# amica.net
KiCad netlist of a schematic drawn in EAGLE
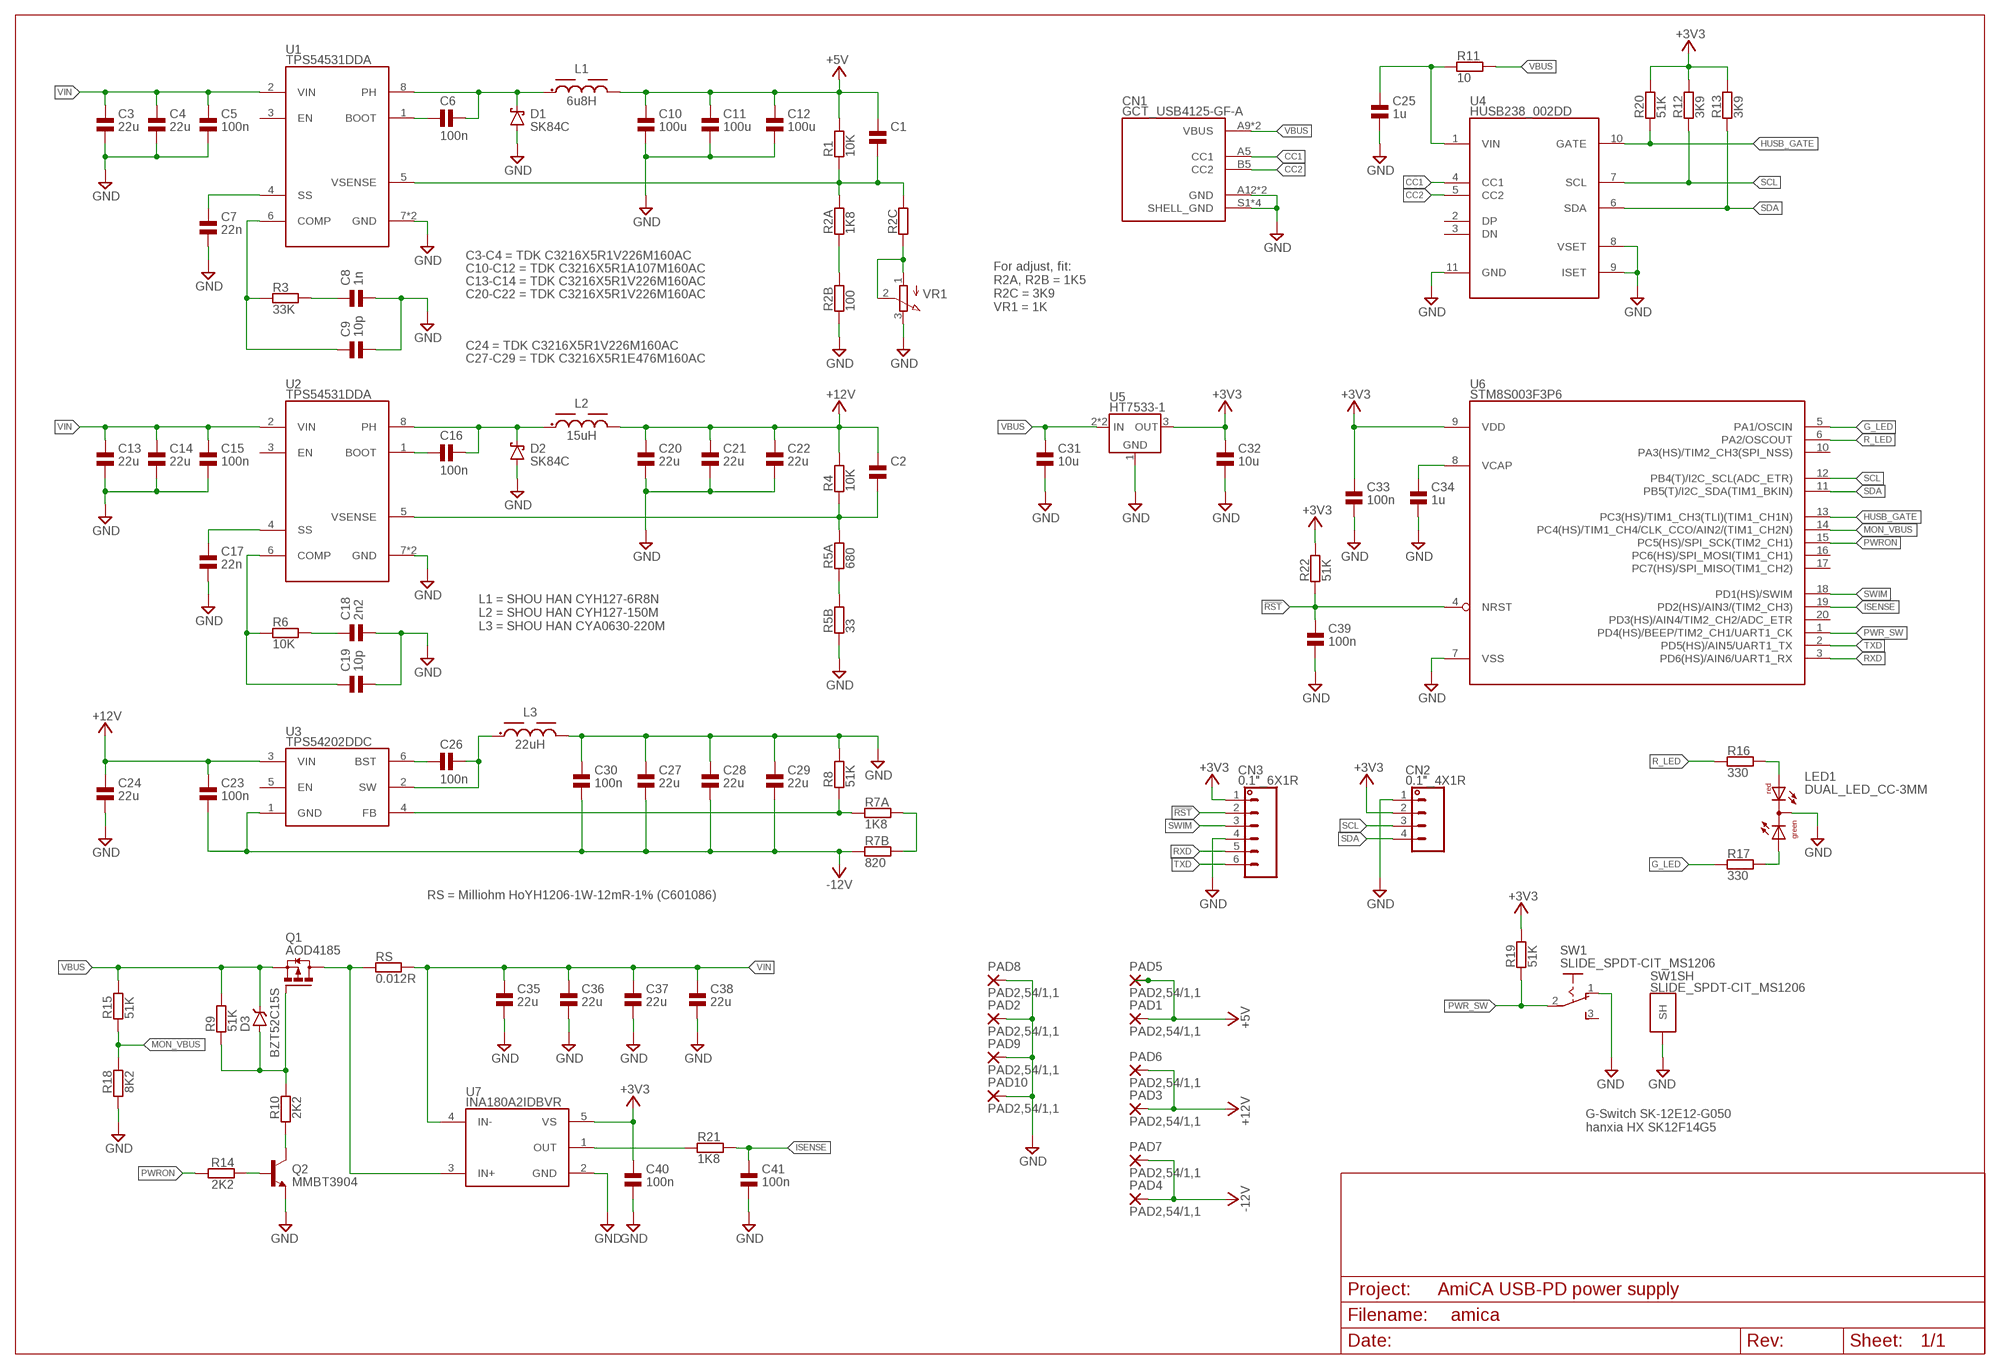
[diagram p0: schematic, sheet 1]

(export (version "E")
  (design (tool "Eeschema 10.0.6"))
  (components
    (comp (ref "C1")
      (value "CAP_NPOL-0603")
      (footprint "eagle-import:0603")
      (libsource (lib "eagle-import") (part "CAP_NPOL0603-"))
    )
    (comp (ref "C2")
      (value "CAP_NPOL-0603")
      (footprint "eagle-import:0603")
      (libsource (lib "eagle-import") (part "CAP_NPOL0603-"))
    )
    (comp (ref "C3")
      (value "22u")
      (footprint "eagle-import:1206")
      (fields (field (name "LCSC_PART") "C12891"))
      (libsource (lib "eagle-import") (part "CAP_NPOL1206-"))
    )
    (comp (ref "C4")
      (value "22u")
      (footprint "eagle-import:1206")
      (fields (field (name "LCSC_PART") "C12891"))
      (libsource (lib "eagle-import") (part "CAP_NPOL1206-"))
    )
    (comp (ref "C5")
      (value "100n")
      (footprint "eagle-import:0603")
      (fields (field (name "LCSC_PART") "C14663"))
      (libsource (lib "eagle-import") (part "CAP_NPOL0603-"))
    )
    (comp (ref "C6")
      (value "100n")
      (footprint "eagle-import:0603")
      (fields (field (name "LCSC_PART") "C14663"))
      (libsource (lib "eagle-import") (part "CAP_NPOL0603-"))
    )
    (comp (ref "C7")
      (value "22n")
      (footprint "eagle-import:0603")
      (fields (field (name "LCSC_PART") "C21122"))
      (libsource (lib "eagle-import") (part "CAP_NPOL0603-"))
    )
    (comp (ref "C8")
      (value "1n")
      (footprint "eagle-import:0603")
      (fields (field (name "LCSC_PART") "C1588"))
      (libsource (lib "eagle-import") (part "CAP_NPOL0603-"))
    )
    (comp (ref "C9")
      (value "10p")
      (footprint "eagle-import:0603")
      (fields (field (name "LCSC_PART") "C1634"))
      (libsource (lib "eagle-import") (part "CAP_NPOL0603-"))
    )
    (comp (ref "C10")
      (value "100u")
      (footprint "eagle-import:1206")
      (fields (field (name "LCSC_PART") "C15008"))
      (libsource (lib "eagle-import") (part "CAP_NPOL1206-"))
    )
    (comp (ref "C11")
      (value "100u")
      (footprint "eagle-import:1206")
      (fields (field (name "LCSC_PART") "C15008"))
      (libsource (lib "eagle-import") (part "CAP_NPOL1206-"))
    )
    (comp (ref "C12")
      (value "100u")
      (footprint "eagle-import:1206")
      (fields (field (name "LCSC_PART") "C15008"))
      (libsource (lib "eagle-import") (part "CAP_NPOL1206-"))
    )
    (comp (ref "C13")
      (value "22u")
      (footprint "eagle-import:1206")
      (fields (field (name "LCSC_PART") "C12891"))
      (libsource (lib "eagle-import") (part "CAP_NPOL1206-"))
    )
    (comp (ref "C14")
      (value "22u")
      (footprint "eagle-import:1206")
      (fields (field (name "LCSC_PART") "C12891"))
      (libsource (lib "eagle-import") (part "CAP_NPOL1206-"))
    )
    (comp (ref "C15")
      (value "100n")
      (footprint "eagle-import:0603")
      (fields (field (name "LCSC_PART") "C14663"))
      (libsource (lib "eagle-import") (part "CAP_NPOL0603-"))
    )
    (comp (ref "C16")
      (value "100n")
      (footprint "eagle-import:0603")
      (fields (field (name "LCSC_PART") "C14663"))
      (libsource (lib "eagle-import") (part "CAP_NPOL0603-"))
    )
    (comp (ref "C17")
      (value "22n")
      (footprint "eagle-import:0603")
      (fields (field (name "LCSC_PART") "C21122"))
      (libsource (lib "eagle-import") (part "CAP_NPOL0603-"))
    )
    (comp (ref "C18")
      (value "2n2")
      (footprint "eagle-import:0603")
      (fields (field (name "LCSC_PART") "C1604"))
      (libsource (lib "eagle-import") (part "CAP_NPOL0603-"))
    )
    (comp (ref "C19")
      (value "10p")
      (footprint "eagle-import:0603")
      (fields (field (name "LCSC_PART") "C1634"))
      (libsource (lib "eagle-import") (part "CAP_NPOL0603-"))
    )
    (comp (ref "C20")
      (value "22u")
      (footprint "eagle-import:1206")
      (fields (field (name "LCSC_PART") "C12891"))
      (libsource (lib "eagle-import") (part "CAP_NPOL1206-"))
    )
    (comp (ref "C21")
      (value "22u")
      (footprint "eagle-import:1206")
      (fields (field (name "LCSC_PART") "C12891"))
      (libsource (lib "eagle-import") (part "CAP_NPOL1206-"))
    )
    (comp (ref "C22")
      (value "22u")
      (footprint "eagle-import:1206")
      (fields (field (name "LCSC_PART") "C12891"))
      (libsource (lib "eagle-import") (part "CAP_NPOL1206-"))
    )
    (comp (ref "C23")
      (value "100n")
      (footprint "eagle-import:0603")
      (fields (field (name "LCSC_PART") "C14663"))
      (libsource (lib "eagle-import") (part "CAP_NPOL0603-"))
    )
    (comp (ref "C24")
      (value "22u")
      (footprint "eagle-import:1206")
      (fields (field (name "LCSC_PART") "C12891"))
      (libsource (lib "eagle-import") (part "CAP_NPOL1206-"))
    )
    (comp (ref "C25")
      (value "1u")
      (footprint "eagle-import:0603")
      (fields (field (name "LCSC_PART") "C15849"))
      (libsource (lib "eagle-import") (part "CAP_NPOL0603-"))
    )
    (comp (ref "C26")
      (value "100n")
      (footprint "eagle-import:0603")
      (fields (field (name "LCSC_PART") "C14663"))
      (libsource (lib "eagle-import") (part "CAP_NPOL0603-"))
    )
    (comp (ref "C27")
      (value "22u")
      (footprint "eagle-import:1206")
      (fields (field (name "LCSC_PART") "C12891"))
      (libsource (lib "eagle-import") (part "CAP_NPOL1206-"))
    )
    (comp (ref "C28")
      (value "22u")
      (footprint "eagle-import:1206")
      (fields (field (name "LCSC_PART") "C12891"))
      (libsource (lib "eagle-import") (part "CAP_NPOL1206-"))
    )
    (comp (ref "C29")
      (value "22u")
      (footprint "eagle-import:1206")
      (fields (field (name "LCSC_PART") "C12891"))
      (libsource (lib "eagle-import") (part "CAP_NPOL1206-"))
    )
    (comp (ref "C30")
      (value "100n")
      (footprint "eagle-import:0603")
      (fields (field (name "LCSC_PART") "C14663"))
      (libsource (lib "eagle-import") (part "CAP_NPOL0603-"))
    )
    (comp (ref "C31")
      (value "10u")
      (footprint "eagle-import:0805")
      (fields (field (name "LCSC_PART") "C15850"))
      (libsource (lib "eagle-import") (part "CAP_NPOL0805-"))
    )
    (comp (ref "C32")
      (value "10u")
      (footprint "eagle-import:0603")
      (fields (field (name "LCSC_PART") "C19702"))
      (libsource (lib "eagle-import") (part "CAP_NPOL0603-"))
    )
    (comp (ref "C33")
      (value "100n")
      (footprint "eagle-import:0603")
      (fields (field (name "LCSC_PART") "C14663"))
      (libsource (lib "eagle-import") (part "CAP_NPOL0603-"))
    )
    (comp (ref "C34")
      (value "1u")
      (footprint "eagle-import:0603")
      (fields (field (name "LCSC_PART") "C15849"))
      (libsource (lib "eagle-import") (part "CAP_NPOL0603-"))
    )
    (comp (ref "C35")
      (value "22u")
      (footprint "eagle-import:1206")
      (fields (field (name "LCSC_PART") "C12891"))
      (libsource (lib "eagle-import") (part "CAP_NPOL1206-"))
    )
    (comp (ref "C36")
      (value "22u")
      (footprint "eagle-import:1206")
      (fields (field (name "LCSC_PART") "C12891"))
      (libsource (lib "eagle-import") (part "CAP_NPOL1206-"))
    )
    (comp (ref "C37")
      (value "22u")
      (footprint "eagle-import:1206")
      (fields (field (name "LCSC_PART") "C12891"))
      (libsource (lib "eagle-import") (part "CAP_NPOL1206-"))
    )
    (comp (ref "C38")
      (value "22u")
      (footprint "eagle-import:1206")
      (fields (field (name "LCSC_PART") "C12891"))
      (libsource (lib "eagle-import") (part "CAP_NPOL1206-"))
    )
    (comp (ref "C39")
      (value "100n")
      (footprint "eagle-import:0603")
      (fields (field (name "LCSC_PART") "C14663"))
      (libsource (lib "eagle-import") (part "CAP_NPOL0603-"))
    )
    (comp (ref "C40")
      (value "100n")
      (footprint "eagle-import:0603")
      (fields (field (name "LCSC_PART") "C14663"))
      (libsource (lib "eagle-import") (part "CAP_NPOL0603-"))
    )
    (comp (ref "C41")
      (value "100n")
      (footprint "eagle-import:0603")
      (fields (field (name "LCSC_PART") "C14663"))
      (libsource (lib "eagle-import") (part "CAP_NPOL0603-"))
    )
    (comp (ref "CN1")
      (value "GCT_USB4125-GF-A")
      (footprint "eagle-import:GCT_USB4125-GF-A-0190_REVA2")
      (fields (field (name "LCSC_PART") "C18357552"))
      (libsource (lib "eagle-import") (part "USB-C-6P_GCT_USB4125-GF-A"))
    )
    (comp (ref "CN2")
      (value "0.1\"_4X1R")
      (footprint "eagle-import:0.1__4X1-ROUND")
      (libsource (lib "eagle-import") (part "0.1{dblquote}_4X1R"))
    )
    (comp (ref "CN3")
      (value "0.1\"_6X1R")
      (footprint "eagle-import:0.1__6X1-ROUND")
      (libsource (lib "eagle-import") (part "0.1{dblquote}_6X1R"))
    )
    (comp (ref "D1")
      (value "SK84C")
      (footprint "eagle-import:SMC")
      (fields (field (name "LCSC_PART") "C28646293"))
      (libsource (lib "eagle-import") (part "-SHOTTKY_?SMC"))
    )
    (comp (ref "D2")
      (value "SK84C")
      (footprint "eagle-import:SMC")
      (fields (field (name "LCSC_PART") "C28646293"))
      (libsource (lib "eagle-import") (part "-SHOTTKY_?SMC"))
    )
    (comp (ref "D3")
      (value "BZT52C15S")
      (footprint "eagle-import:SOD323F")
      (fields (field (name "LCSC_PART") "C19077448"))
      (libsource (lib "eagle-import") (part "-ZENER_?SOD323F"))
    )
    (comp (ref "L1")
      (value "6u8H")
      (footprint "eagle-import:SHOUHAN_CYH125")
      (fields (field (name "LCSC_PART") "C2929498"))
      (libsource (lib "eagle-import") (part "LSHOUHAN_CYH125-"))
    )
    (comp (ref "L2")
      (value "15uH")
      (footprint "eagle-import:SHOUHAN_CYH125")
      (fields (field (name "LCSC_PART") "C2929500"))
      (libsource (lib "eagle-import") (part "LSHOUHAN_CYH125-"))
    )
    (comp (ref "L3")
      (value "22uH")
      (footprint "eagle-import:SHOUHAN_CYA0630")
      (fields (field (name "LCSC_PART") "C5189960"))
      (libsource (lib "eagle-import") (part "LSHOUHAN_CYA0630-"))
    )
    (comp (ref "LED1")
      (value "DUAL_LED_CC-3MM")
      (footprint "eagle-import:DUOLED-3MM")
      (libsource (lib "eagle-import") (part "DUAL_LED_CC3MM-"))
    )
    (comp (ref "PAD1")
      (value "PAD2,54/1,1")
      (footprint "eagle-import:2,54_1,1")
      (libsource (lib "eagle-import") (part "PAD2,54/1,1"))
    )
    (comp (ref "PAD2")
      (value "PAD2,54/1,1")
      (footprint "eagle-import:2,54_1,1")
      (libsource (lib "eagle-import") (part "PAD2,54/1,1"))
    )
    (comp (ref "PAD3")
      (value "PAD2,54/1,1")
      (footprint "eagle-import:2,54_1,1")
      (libsource (lib "eagle-import") (part "PAD2,54/1,1"))
    )
    (comp (ref "PAD4")
      (value "PAD2,54/1,1")
      (footprint "eagle-import:2,54_1,1")
      (libsource (lib "eagle-import") (part "PAD2,54/1,1"))
    )
    (comp (ref "PAD5")
      (value "PAD2,54/1,1")
      (footprint "eagle-import:2,54_1,1")
      (libsource (lib "eagle-import") (part "PAD2,54/1,1"))
    )
    (comp (ref "PAD6")
      (value "PAD2,54/1,1")
      (footprint "eagle-import:2,54_1,1")
      (libsource (lib "eagle-import") (part "PAD2,54/1,1"))
    )
    (comp (ref "PAD7")
      (value "PAD2,54/1,1")
      (footprint "eagle-import:2,54_1,1")
      (libsource (lib "eagle-import") (part "PAD2,54/1,1"))
    )
    (comp (ref "PAD8")
      (value "PAD2,54/1,1")
      (footprint "eagle-import:2,54_1,1")
      (libsource (lib "eagle-import") (part "PAD2,54/1,1"))
    )
    (comp (ref "PAD9")
      (value "PAD2,54/1,1")
      (footprint "eagle-import:2,54_1,1")
      (libsource (lib "eagle-import") (part "PAD2,54/1,1"))
    )
    (comp (ref "PAD10")
      (value "PAD2,54/1,1")
      (footprint "eagle-import:2,54_1,1")
      (libsource (lib "eagle-import") (part "PAD2,54/1,1"))
    )
    (comp (ref "Q1")
      (value "AOD4185")
      (footprint "eagle-import:DPAK")
      (fields (field (name "LCSC_PART") "C400894"))
      (libsource (lib "eagle-import") (part "-PMOS_?DPAK"))
    )
    (comp (ref "Q2")
      (value "MMBT3904")
      (footprint "eagle-import:SOT23")
      (fields (field (name "LCSC_PART") "C7420353"))
      (libsource (lib "eagle-import") (part "-NPN_?SOT23"))
    )
    (comp (ref "R1")
      (value "10K")
      (footprint "eagle-import:0603")
      (fields (field (name "LCSC_PART") "C25804"))
      (libsource (lib "eagle-import") (part "RESSMD_0603-"))
    )
    (comp (ref "R2A")
      (value "1K8")
      (footprint "eagle-import:0603")
      (fields (field (name "LCSC_PART") "C4177"))
      (libsource (lib "eagle-import") (part "RESSMD_0603-"))
    )
    (comp (ref "R2B")
      (value "100")
      (footprint "eagle-import:0603")
      (fields (field (name "LCSC_PART") "C22775"))
      (libsource (lib "eagle-import") (part "RESSMD_0603-"))
    )
    (comp (ref "R2C")
      (value "RES-SMD_0603")
      (footprint "eagle-import:0603")
      (libsource (lib "eagle-import") (part "RESSMD_0603-"))
    )
    (comp (ref "R3")
      (value "33K")
      (footprint "eagle-import:0603")
      (fields (field (name "LCSC_PART") "C4216"))
      (libsource (lib "eagle-import") (part "RESSMD_0603-"))
    )
    (comp (ref "R4")
      (value "10K")
      (footprint "eagle-import:0603")
      (fields (field (name "LCSC_PART") "C25804"))
      (libsource (lib "eagle-import") (part "RESSMD_0603-"))
    )
    (comp (ref "R5A")
      (value "680")
      (footprint "eagle-import:0603")
      (fields (field (name "LCSC_PART") "C23228"))
      (libsource (lib "eagle-import") (part "RESSMD_0603-"))
    )
    (comp (ref "R5B")
      (value "33")
      (footprint "eagle-import:0603")
      (fields (field (name "LCSC_PART") "C23140"))
      (libsource (lib "eagle-import") (part "RESSMD_0603-"))
    )
    (comp (ref "R6")
      (value "10K")
      (footprint "eagle-import:0603")
      (fields (field (name "LCSC_PART") "C25804"))
      (libsource (lib "eagle-import") (part "RESSMD_0603-"))
    )
    (comp (ref "R7A")
      (value "1K8")
      (footprint "eagle-import:0603")
      (fields (field (name "LCSC_PART") "C4177"))
      (libsource (lib "eagle-import") (part "RESSMD_0603-"))
    )
    (comp (ref "R7B")
      (value "820")
      (footprint "eagle-import:0603")
      (fields (field (name "LCSC_PART") "C23253"))
      (libsource (lib "eagle-import") (part "RESSMD_0603-"))
    )
    (comp (ref "R8")
      (value "51K")
      (footprint "eagle-import:0603")
      (fields (field (name "LCSC_PART") "C23196"))
      (libsource (lib "eagle-import") (part "RESSMD_0603-"))
    )
    (comp (ref "R9")
      (value "51K")
      (footprint "eagle-import:0603")
      (fields (field (name "LCSC_PART") "C23196"))
      (libsource (lib "eagle-import") (part "RESSMD_0603-"))
    )
    (comp (ref "R10")
      (value "2K2")
      (footprint "eagle-import:0603")
      (fields (field (name "LCSC_PART") "C4190"))
      (libsource (lib "eagle-import") (part "RESSMD_0603-"))
    )
    (comp (ref "R11")
      (value "10")
      (footprint "eagle-import:0805")
      (fields (field (name "LCSC_PART") "C17415"))
      (libsource (lib "eagle-import") (part "RESSMD_0805-"))
    )
    (comp (ref "R12")
      (value "3K9")
      (footprint "eagle-import:0603")
      (fields (field (name "LCSC_PART") "C23018"))
      (libsource (lib "eagle-import") (part "RESSMD_0603-"))
    )
    (comp (ref "R13")
      (value "3K9")
      (footprint "eagle-import:0603")
      (fields (field (name "LCSC_PART") "C23018"))
      (libsource (lib "eagle-import") (part "RESSMD_0603-"))
    )
    (comp (ref "R14")
      (value "2K2")
      (footprint "eagle-import:0603")
      (fields (field (name "LCSC_PART") "C4190"))
      (libsource (lib "eagle-import") (part "RESSMD_0603-"))
    )
    (comp (ref "R15")
      (value "51K")
      (footprint "eagle-import:0603")
      (fields (field (name "LCSC_PART") "C23196"))
      (libsource (lib "eagle-import") (part "RESSMD_0603-"))
    )
    (comp (ref "R16")
      (value "330")
      (footprint "eagle-import:0603")
      (fields (field (name "LCSC_PART") "C23138"))
      (libsource (lib "eagle-import") (part "RESSMD_0603-"))
    )
    (comp (ref "R17")
      (value "330")
      (footprint "eagle-import:0603")
      (fields (field (name "LCSC_PART") "C23138"))
      (libsource (lib "eagle-import") (part "RESSMD_0603-"))
    )
    (comp (ref "R18")
      (value "8K2")
      (footprint "eagle-import:0603")
      (fields (field (name "LCSC_PART") "C25981"))
      (libsource (lib "eagle-import") (part "RESSMD_0603-"))
    )
    (comp (ref "R19")
      (value "51K")
      (footprint "eagle-import:0603")
      (fields (field (name "LCSC_PART") "C23196"))
      (libsource (lib "eagle-import") (part "RESSMD_0603-"))
    )
    (comp (ref "R20")
      (value "51K")
      (footprint "eagle-import:0603")
      (fields (field (name "LCSC_PART") "C23196"))
      (libsource (lib "eagle-import") (part "RESSMD_0603-"))
    )
    (comp (ref "R21")
      (value "1K8")
      (footprint "eagle-import:0603")
      (fields (field (name "LCSC_PART") "C4177"))
      (libsource (lib "eagle-import") (part "RESSMD_0603-"))
    )
    (comp (ref "R22")
      (value "51K")
      (footprint "eagle-import:0603")
      (fields (field (name "LCSC_PART") "C23196"))
      (libsource (lib "eagle-import") (part "RESSMD_0603-"))
    )
    (comp (ref "RS")
      (value "0.012R")
      (footprint "eagle-import:1206")
      (fields (field (name "LCSC_PART") "C601086"))
      (libsource (lib "eagle-import") (part "RESSMD_1206-"))
    )
    (comp (ref "SW1")
      (value "SLIDE_SPDT-CIT_MS1206")
      (footprint "eagle-import:CIT_MS1206")
      (fields (field (name "LCSC_PART") "C2848870"))
      (libsource (lib "eagle-import") (part "SLIDE_SPDTCIT_MS1206-"))
    )
    (comp (ref "U1")
      (value "TPS54531DDA")
      (footprint "eagle-import:SO08-EP")
      (fields (field (name "LCSC_PART") "C50605"))
      (libsource (lib "eagle-import") (part "TPS54531DDA"))
    )
    (comp (ref "U2")
      (value "TPS54531DDA")
      (footprint "eagle-import:SO08-EP")
      (fields (field (name "LCSC_PART") "C50605"))
      (libsource (lib "eagle-import") (part "TPS54531DDA"))
    )
    (comp (ref "U3")
      (value "TPS54202DDC")
      (footprint "eagle-import:SOT23-6")
      (fields (field (name "LCSC_PART") "C191884"))
      (libsource (lib "eagle-import") (part "TPS54202DDC"))
    )
    (comp (ref "U4")
      (value "HUSB238_002DD")
      (footprint "eagle-import:DFN10-3X3")
      (fields (field (name "LCSC_PART") "C7471904"))
      (libsource (lib "eagle-import") (part "HUSB238DD_002"))
    )
    (comp (ref "U5")
      (value "HT7533-1")
      (footprint "eagle-import:SOT89")
      (fields (field (name "LCSC_PART") "C14289"))
      (libsource (lib "eagle-import") (part "HT75-133"))
    )
    (comp (ref "U6")
      (value "STM8S003F3P6")
      (footprint "eagle-import:TSSOP20")
      (fields (field (name "LCSC_PART") "C52717"))
      (libsource (lib "eagle-import") (part "STM8S003F3?6P"))
    )
    (comp (ref "U7")
      (value "INA180A2IDBVR")
      (footprint "eagle-import:SOT23-5")
      (fields (field (name "LCSC_PART") "C192764"))
      (libsource (lib "eagle-import") (part "INA180ADBV2"))
    )
    (comp (ref "VR1")
      (value "TRIMMER-BOURNS_3362P")
      (footprint "eagle-import:TRIM_3362P-1")
      (libsource (lib "eagle-import") (part "TRIMMERBOURNS_3362P-"))
    )
  )
  (nets
    (net (code "1") (name "+3V3") (class "Default")
      (node (ref "C32") (pin "1") (pinfunction "1_1") (pintype "passive"))
      (node (ref "C33") (pin "1") (pinfunction "1_1") (pintype "passive"))
      (node (ref "C40") (pin "1") (pinfunction "1_1") (pintype "passive"))
      (node (ref "CN2") (pin "2") (pinfunction "2_2") (pintype "passive"))
      (node (ref "CN3") (pin "1") (pinfunction "1_1") (pintype "passive"))
      (node (ref "R12") (pin "2") (pinfunction "2_2") (pintype "passive"))
      (node (ref "R13") (pin "2") (pinfunction "2_2") (pintype "passive"))
      (node (ref "R19") (pin "2") (pinfunction "2_2") (pintype "passive"))
      (node (ref "R20") (pin "2") (pinfunction "2_2") (pintype "passive"))
      (node (ref "R22") (pin "2") (pinfunction "2_2") (pintype "passive"))
      (node (ref "U5") (pin "3") (pinfunction "OUT_3") (pintype "passive"))
      (node (ref "U6") (pin "9") (pinfunction "VDD_9") (pintype "power_in"))
      (node (ref "U7") (pin "5") (pinfunction "VS_5") (pintype "power_in"))
    )
    (net (code "2") (name "+5V") (class "Default")
      (node (ref "C1") (pin "1") (pinfunction "1_1") (pintype "passive"))
      (node (ref "C10") (pin "1") (pinfunction "1_1") (pintype "passive"))
      (node (ref "C11") (pin "1") (pinfunction "1_1") (pintype "passive"))
      (node (ref "C12") (pin "1") (pinfunction "1_1") (pintype "passive"))
      (node (ref "L1") (pin "P$2") (pinfunction "2_P$2") (pintype "passive"))
      (node (ref "PAD1") (pin "1") (pinfunction "P_1") (pintype "passive"))
      (node (ref "PAD5") (pin "1") (pinfunction "P_1") (pintype "passive"))
      (node (ref "R1") (pin "2") (pinfunction "2_2") (pintype "passive"))
    )
    (net (code "3") (name "+12V") (class "Default")
      (node (ref "C2") (pin "1") (pinfunction "1_1") (pintype "passive"))
      (node (ref "C20") (pin "1") (pinfunction "1_1") (pintype "passive"))
      (node (ref "C21") (pin "1") (pinfunction "1_1") (pintype "passive"))
      (node (ref "C22") (pin "1") (pinfunction "1_1") (pintype "passive"))
      (node (ref "C23") (pin "1") (pinfunction "1_1") (pintype "passive"))
      (node (ref "C24") (pin "1") (pinfunction "1_1") (pintype "passive"))
      (node (ref "L2") (pin "P$2") (pinfunction "2_P$2") (pintype "passive"))
      (node (ref "PAD3") (pin "1") (pinfunction "P_1") (pintype "passive"))
      (node (ref "PAD6") (pin "1") (pinfunction "P_1") (pintype "passive"))
      (node (ref "R4") (pin "2") (pinfunction "2_2") (pintype "passive"))
      (node (ref "U3") (pin "3") (pinfunction "VIN_3") (pintype "passive"))
    )
    (net (code "4") (name "-12V") (class "Default")
      (node (ref "C23") (pin "2") (pinfunction "2_2") (pintype "passive"))
      (node (ref "C27") (pin "2") (pinfunction "2_2") (pintype "passive"))
      (node (ref "C28") (pin "2") (pinfunction "2_2") (pintype "passive"))
      (node (ref "C29") (pin "2") (pinfunction "2_2") (pintype "passive"))
      (node (ref "C30") (pin "2") (pinfunction "2_2") (pintype "passive"))
      (node (ref "PAD4") (pin "1") (pinfunction "P_1") (pintype "passive"))
      (node (ref "PAD7") (pin "1") (pinfunction "P_1") (pintype "passive"))
      (node (ref "R7B") (pin "1") (pinfunction "1_1") (pintype "passive"))
      (node (ref "U3") (pin "1") (pinfunction "GND_1") (pintype "passive"))
    )
    (net (code "5") (name "/~{RST}") (class "Default")
      (node (ref "C39") (pin "1") (pinfunction "1_1") (pintype "passive"))
      (node (ref "CN3") (pin "2") (pinfunction "2_2") (pintype "passive"))
      (node (ref "R22") (pin "1") (pinfunction "1_1") (pintype "passive"))
      (node (ref "U6") (pin "4") (pinfunction "NRST_4") (pintype "bidirectional"))
    )
    (net (code "6") (name "CC1") (class "Default")
      (node (ref "CN1") (pin "A5") (pinfunction "CC1_A5") (pintype "bidirectional"))
      (node (ref "U4") (pin "4") (pinfunction "CC1_4") (pintype "bidirectional"))
    )
    (net (code "7") (name "CC2") (class "Default")
      (node (ref "CN1") (pin "B5") (pinfunction "CC2_B5") (pintype "bidirectional"))
      (node (ref "U4") (pin "5") (pinfunction "CC2_5") (pintype "bidirectional"))
    )
    (net (code "8") (name "GND") (class "Default")
      (node (ref "C10") (pin "2") (pinfunction "2_2") (pintype "passive"))
      (node (ref "C11") (pin "2") (pinfunction "2_2") (pintype "passive"))
      (node (ref "C12") (pin "2") (pinfunction "2_2") (pintype "passive"))
      (node (ref "C13") (pin "2") (pinfunction "2_2") (pintype "passive"))
      (node (ref "C14") (pin "2") (pinfunction "2_2") (pintype "passive"))
      (node (ref "C15") (pin "2") (pinfunction "2_2") (pintype "passive"))
      (node (ref "C17") (pin "2") (pinfunction "2_2") (pintype "passive"))
      (node (ref "C18") (pin "2") (pinfunction "2_2") (pintype "passive"))
      (node (ref "C19") (pin "2") (pinfunction "2_2") (pintype "passive"))
      (node (ref "C20") (pin "2") (pinfunction "2_2") (pintype "passive"))
      (node (ref "C21") (pin "2") (pinfunction "2_2") (pintype "passive"))
      (node (ref "C22") (pin "2") (pinfunction "2_2") (pintype "passive"))
      (node (ref "C24") (pin "2") (pinfunction "2_2") (pintype "passive"))
      (node (ref "C25") (pin "2") (pinfunction "2_2") (pintype "passive"))
      (node (ref "C27") (pin "1") (pinfunction "1_1") (pintype "passive"))
      (node (ref "C28") (pin "1") (pinfunction "1_1") (pintype "passive"))
      (node (ref "C29") (pin "1") (pinfunction "1_1") (pintype "passive"))
      (node (ref "C3") (pin "2") (pinfunction "2_2") (pintype "passive"))
      (node (ref "C30") (pin "1") (pinfunction "1_1") (pintype "passive"))
      (node (ref "C31") (pin "2") (pinfunction "2_2") (pintype "passive"))
      (node (ref "C32") (pin "2") (pinfunction "2_2") (pintype "passive"))
      (node (ref "C33") (pin "2") (pinfunction "2_2") (pintype "passive"))
      (node (ref "C34") (pin "2") (pinfunction "2_2") (pintype "passive"))
      (node (ref "C35") (pin "2") (pinfunction "2_2") (pintype "passive"))
      (node (ref "C36") (pin "2") (pinfunction "2_2") (pintype "passive"))
      (node (ref "C37") (pin "2") (pinfunction "2_2") (pintype "passive"))
      (node (ref "C38") (pin "2") (pinfunction "2_2") (pintype "passive"))
      (node (ref "C39") (pin "2") (pinfunction "2_2") (pintype "passive"))
      (node (ref "C4") (pin "2") (pinfunction "2_2") (pintype "passive"))
      (node (ref "C40") (pin "2") (pinfunction "2_2") (pintype "passive"))
      (node (ref "C41") (pin "2") (pinfunction "2_2") (pintype "passive"))
      (node (ref "C5") (pin "2") (pinfunction "2_2") (pintype "passive"))
      (node (ref "C7") (pin "2") (pinfunction "2_2") (pintype "passive"))
      (node (ref "C8") (pin "2") (pinfunction "2_2") (pintype "passive"))
      (node (ref "C9") (pin "2") (pinfunction "2_2") (pintype "passive"))
      (node (ref "CN1") (pin "A12") (pinfunction "GND_A12") (pintype "power_in"))
      (node (ref "CN1") (pin "B12") (pinfunction "GND_B12") (pintype "power_in"))
      (node (ref "CN1") (pin "S1") (pinfunction "SHELL_GND_S1") (pintype "power_in"))
      (node (ref "CN1") (pin "S2") (pinfunction "SHELL_GND_S2") (pintype "power_in"))
      (node (ref "CN1") (pin "S3") (pinfunction "SHELL_GND_S3") (pintype "power_in"))
      (node (ref "CN1") (pin "S4") (pinfunction "SHELL_GND_S4") (pintype "power_in"))
      (node (ref "CN2") (pin "1") (pinfunction "1_1") (pintype "passive"))
      (node (ref "CN3") (pin "4") (pinfunction "4_4") (pintype "passive"))
      (node (ref "D1") (pin "A") (pinfunction "A_A") (pintype "passive"))
      (node (ref "D2") (pin "A") (pinfunction "A_A") (pintype "passive"))
      (node (ref "L3") (pin "P$2") (pinfunction "2_P$2") (pintype "passive"))
      (node (ref "LED1") (pin "COM") (pinfunction "C_COM") (pintype "passive"))
      (node (ref "PAD10") (pin "1") (pinfunction "P_1") (pintype "passive"))
      (node (ref "PAD2") (pin "1") (pinfunction "P_1") (pintype "passive"))
      (node (ref "PAD8") (pin "1") (pinfunction "P_1") (pintype "passive"))
      (node (ref "PAD9") (pin "1") (pinfunction "P_1") (pintype "passive"))
      (node (ref "Q2") (pin "2") (pinfunction "E_2") (pintype "passive"))
      (node (ref "R18") (pin "2") (pinfunction "2_2") (pintype "passive"))
      (node (ref "R2B") (pin "1") (pinfunction "1_1") (pintype "passive"))
      (node (ref "R5B") (pin "1") (pinfunction "1_1") (pintype "passive"))
      (node (ref "R8") (pin "2") (pinfunction "2_2") (pintype "passive"))
      (node (ref "SW1") (pin "1") (pinfunction "O_1") (pintype "passive"))
      (node (ref "SW1") (pin "GND@1") (pinfunction "SH_GND@1") (pintype "passive"))
      (node (ref "SW1") (pin "GND@2") (pinfunction "SH_GND@2") (pintype "passive"))
      (node (ref "U1") (pin "7") (pinfunction "GND_7") (pintype "passive"))
      (node (ref "U1") (pin "PAD") (pinfunction "GND_PAD") (pintype "passive"))
      (node (ref "U2") (pin "7") (pinfunction "GND_7") (pintype "passive"))
      (node (ref "U2") (pin "PAD") (pinfunction "GND_PAD") (pintype "passive"))
      (node (ref "U4") (pin "11") (pinfunction "GND_11") (pintype "power_in"))
      (node (ref "U4") (pin "8") (pinfunction "VSET_8") (pintype "passive"))
      (node (ref "U4") (pin "9") (pinfunction "ISET_9") (pintype "passive"))
      (node (ref "U5") (pin "1") (pinfunction "GND_1") (pintype "passive"))
      (node (ref "U6") (pin "7") (pinfunction "VSS_7") (pintype "power_in"))
      (node (ref "U7") (pin "2") (pinfunction "GND_2") (pintype "power_in"))
      (node (ref "VR1") (pin "3") (pinfunction "CW_3") (pintype "passive"))
    )
    (net (code "9") (name "G_LED") (class "Default")
      (node (ref "R17") (pin "1") (pinfunction "1_1") (pintype "passive"))
      (node (ref "U6") (pin "5") (pinfunction "PA1/OSCIN_5") (pintype "bidirectional"))
    )
    (net (code "10") (name "HUSB_GATE") (class "Default")
      (node (ref "R20") (pin "1") (pinfunction "1_1") (pintype "passive"))
      (node (ref "U4") (pin "10") (pinfunction "GATE_10") (pintype "passive"))
      (node (ref "U6") (pin "13") (pinfunction "PC3(HS)/TIM1_CH3(TLI)(TIM1_CH1N)_13") (pintype "bidirectional"))
    )
    (net (code "11") (name "ISENSE") (class "Default")
      (node (ref "C41") (pin "1") (pinfunction "1_1") (pintype "passive"))
      (node (ref "R21") (pin "2") (pinfunction "2_2") (pintype "passive"))
      (node (ref "U6") (pin "19") (pinfunction "PD2(HS)/AIN3/(TIM2_CH3)_19") (pintype "bidirectional"))
    )
    (net (code "12") (name "MON_VBUS") (class "Default")
      (node (ref "R15") (pin "1") (pinfunction "1_1") (pintype "passive"))
      (node (ref "R18") (pin "1") (pinfunction "1_1") (pintype "passive"))
      (node (ref "U6") (pin "14") (pinfunction "PC4(HS)/TIM1_CH4/CLK_CCO/AIN2/(TIM1_CH2N)_14") (pintype "bidirectional"))
    )
    (net (code "13") (name "Net-(C8-Pad1)") (class "Default")
      (node (ref "C8") (pin "1") (pinfunction "1_1") (pintype "passive"))
      (node (ref "R3") (pin "2") (pinfunction "2_2") (pintype "passive"))
    )
    (net (code "14") (name "Net-(C18-Pad1)") (class "Default")
      (node (ref "C18") (pin "1") (pinfunction "1_1") (pintype "passive"))
      (node (ref "R6") (pin "2") (pinfunction "2_2") (pintype "passive"))
    )
    (net (code "15") (name "Net-(D1-C)") (class "Default")
      (node (ref "C6") (pin "2") (pinfunction "2_2") (pintype "passive"))
      (node (ref "D1") (pin "K") (pinfunction "C_K") (pintype "passive"))
      (node (ref "L1") (pin "P$1") (pinfunction "1_P$1") (pintype "passive"))
      (node (ref "U1") (pin "8") (pinfunction "PH_8") (pintype "passive"))
    )
    (net (code "16") (name "Net-(D2-C)") (class "Default")
      (node (ref "C16") (pin "2") (pinfunction "2_2") (pintype "passive"))
      (node (ref "D2") (pin "K") (pinfunction "C_K") (pintype "passive"))
      (node (ref "L2") (pin "P$1") (pinfunction "1_P$1") (pintype "passive"))
      (node (ref "U2") (pin "8") (pinfunction "PH_8") (pintype "passive"))
    )
    (net (code "17") (name "Net-(L3-1)") (class "Default")
      (node (ref "C26") (pin "2") (pinfunction "2_2") (pintype "passive"))
      (node (ref "L3") (pin "P$1") (pinfunction "1_P$1") (pintype "passive"))
      (node (ref "U3") (pin "2") (pinfunction "SW_2") (pintype "passive"))
    )
    (net (code "18") (name "Net-(LED1-AG)") (class "Default")
      (node (ref "LED1") (pin "1") (pinfunction "AG_1") (pintype "passive"))
      (node (ref "R17") (pin "2") (pinfunction "2_2") (pintype "passive"))
    )
    (net (code "19") (name "Net-(LED1-AR)") (class "Default")
      (node (ref "LED1") (pin "2") (pinfunction "AR_2") (pintype "passive"))
      (node (ref "R16") (pin "2") (pinfunction "2_2") (pintype "passive"))
    )
    (net (code "20") (name "Net-(Q1-D)") (class "Default")
      (node (ref "Q1") (pin "4") (pinfunction "D_4") (pintype "passive"))
      (node (ref "RS") (pin "1") (pinfunction "1_1") (pintype "passive"))
      (node (ref "U7") (pin "3") (pinfunction "IN+_3") (pintype "passive"))
    )
    (net (code "21") (name "Net-(Q1-G)") (class "Default")
      (node (ref "D3") (pin "A") (pinfunction "A_A") (pintype "passive"))
      (node (ref "Q1") (pin "1") (pinfunction "G_1") (pintype "passive"))
      (node (ref "R10") (pin "1") (pinfunction "1_1") (pintype "passive"))
      (node (ref "R9") (pin "1") (pinfunction "1_1") (pintype "passive"))
    )
    (net (code "22") (name "Net-(Q2-B)") (class "Default")
      (node (ref "Q2") (pin "1") (pinfunction "B_1") (pintype "passive"))
      (node (ref "R14") (pin "1") (pinfunction "1_1") (pintype "passive"))
    )
    (net (code "23") (name "Net-(Q2-C)") (class "Default")
      (node (ref "Q2") (pin "3") (pinfunction "C_3") (pintype "passive"))
      (node (ref "R10") (pin "2") (pinfunction "2_2") (pintype "passive"))
    )
    (net (code "24") (name "Net-(R2A-Pad1)") (class "Default")
      (node (ref "R2A") (pin "1") (pinfunction "1_1") (pintype "passive"))
      (node (ref "R2B") (pin "2") (pinfunction "2_2") (pintype "passive"))
    )
    (net (code "25") (name "Net-(R5A-Pad1)") (class "Default")
      (node (ref "R5A") (pin "1") (pinfunction "1_1") (pintype "passive"))
      (node (ref "R5B") (pin "2") (pinfunction "2_2") (pintype "passive"))
    )
    (net (code "26") (name "Net-(R7A-Pad2)") (class "Default")
      (node (ref "R7A") (pin "2") (pinfunction "2_2") (pintype "passive"))
      (node (ref "R7B") (pin "2") (pinfunction "2_2") (pintype "passive"))
    )
    (net (code "27") (name "Net-(U1-BOOT)") (class "Default")
      (node (ref "C6") (pin "1") (pinfunction "1_1") (pintype "passive"))
      (node (ref "U1") (pin "1") (pinfunction "BOOT_1") (pintype "passive"))
    )
    (net (code "28") (name "Net-(U1-COMP)") (class "Default")
      (node (ref "C9") (pin "1") (pinfunction "1_1") (pintype "passive"))
      (node (ref "R3") (pin "1") (pinfunction "1_1") (pintype "passive"))
      (node (ref "U1") (pin "6") (pinfunction "COMP_6") (pintype "passive"))
    )
    (net (code "29") (name "Net-(U1-SS)") (class "Default")
      (node (ref "C7") (pin "1") (pinfunction "1_1") (pintype "passive"))
      (node (ref "U1") (pin "4") (pinfunction "SS_4") (pintype "passive"))
    )
    (net (code "30") (name "Net-(U1-VSENSE)") (class "Default")
      (node (ref "C1") (pin "2") (pinfunction "2_2") (pintype "passive"))
      (node (ref "R1") (pin "1") (pinfunction "1_1") (pintype "passive"))
      (node (ref "R2A") (pin "2") (pinfunction "2_2") (pintype "passive"))
      (node (ref "R2C") (pin "2") (pinfunction "2_2") (pintype "passive"))
      (node (ref "U1") (pin "5") (pinfunction "VSENSE_5") (pintype "passive"))
    )
    (net (code "31") (name "Net-(U2-BOOT)") (class "Default")
      (node (ref "C16") (pin "1") (pinfunction "1_1") (pintype "passive"))
      (node (ref "U2") (pin "1") (pinfunction "BOOT_1") (pintype "passive"))
    )
    (net (code "32") (name "Net-(U2-COMP)") (class "Default")
      (node (ref "C19") (pin "1") (pinfunction "1_1") (pintype "passive"))
      (node (ref "R6") (pin "1") (pinfunction "1_1") (pintype "passive"))
      (node (ref "U2") (pin "6") (pinfunction "COMP_6") (pintype "passive"))
    )
    (net (code "33") (name "Net-(U2-SS)") (class "Default")
      (node (ref "C17") (pin "1") (pinfunction "1_1") (pintype "passive"))
      (node (ref "U2") (pin "4") (pinfunction "SS_4") (pintype "passive"))
    )
    (net (code "34") (name "Net-(U2-VSENSE)") (class "Default")
      (node (ref "C2") (pin "2") (pinfunction "2_2") (pintype "passive"))
      (node (ref "R4") (pin "1") (pinfunction "1_1") (pintype "passive"))
      (node (ref "R5A") (pin "2") (pinfunction "2_2") (pintype "passive"))
      (node (ref "U2") (pin "5") (pinfunction "VSENSE_5") (pintype "passive"))
    )
    (net (code "35") (name "Net-(U3-BST)") (class "Default")
      (node (ref "C26") (pin "1") (pinfunction "1_1") (pintype "passive"))
      (node (ref "U3") (pin "6") (pinfunction "BST_6") (pintype "passive"))
    )
    (net (code "36") (name "Net-(U3-FB)") (class "Default")
      (node (ref "R7A") (pin "1") (pinfunction "1_1") (pintype "passive"))
      (node (ref "R8") (pin "1") (pinfunction "1_1") (pintype "passive"))
      (node (ref "U3") (pin "4") (pinfunction "FB_4") (pintype "passive"))
    )
    (net (code "37") (name "Net-(U4-VIN)") (class "Default")
      (node (ref "C25") (pin "1") (pinfunction "1_1") (pintype "passive"))
      (node (ref "R11") (pin "1") (pinfunction "1_1") (pintype "passive"))
      (node (ref "U4") (pin "1") (pinfunction "VIN_1") (pintype "power_in"))
    )
    (net (code "38") (name "Net-(U6-VCAP)") (class "Default")
      (node (ref "C34") (pin "1") (pinfunction "1_1") (pintype "passive"))
      (node (ref "U6") (pin "8") (pinfunction "VCAP_8") (pintype "power_in"))
    )
    (net (code "39") (name "Net-(U7-OUT)") (class "Default")
      (node (ref "R21") (pin "1") (pinfunction "1_1") (pintype "passive"))
      (node (ref "U7") (pin "1") (pinfunction "OUT_1") (pintype "passive"))
    )
    (net (code "40") (name "Net-(VR1-CCW)") (class "Default")
      (node (ref "R2C") (pin "1") (pinfunction "1_1") (pintype "passive"))
      (node (ref "VR1") (pin "1") (pinfunction "CCW_1") (pintype "passive"))
      (node (ref "VR1") (pin "2") (pinfunction "W_2") (pintype "passive"))
    )
    (net (code "41") (name "PWRON") (class "Default")
      (node (ref "R14") (pin "2") (pinfunction "2_2") (pintype "passive"))
      (node (ref "U6") (pin "15") (pinfunction "PC5(HS)/SPI_SCK(TIM2_CH1)_15") (pintype "bidirectional"))
    )
    (net (code "42") (name "PWR_SW") (class "Default")
      (node (ref "R19") (pin "1") (pinfunction "1_1") (pintype "passive"))
      (node (ref "SW1") (pin "2") (pinfunction "P_2") (pintype "passive"))
      (node (ref "U6") (pin "1") (pinfunction "PD4(HS)/BEEP/TIM2_CH1/UART1_CK_1") (pintype "bidirectional"))
    )
    (net (code "43") (name "RXD") (class "Default")
      (node (ref "CN3") (pin "5") (pinfunction "5_5") (pintype "passive"))
      (node (ref "U6") (pin "3") (pinfunction "PD6(HS)/AIN6/UART1_RX_3") (pintype "bidirectional"))
    )
    (net (code "44") (name "R_LED") (class "Default")
      (node (ref "R16") (pin "1") (pinfunction "1_1") (pintype "passive"))
      (node (ref "U6") (pin "6") (pinfunction "PA2/OSCOUT_6") (pintype "bidirectional"))
    )
    (net (code "45") (name "SCL") (class "Default")
      (node (ref "CN2") (pin "3") (pinfunction "3_3") (pintype "passive"))
      (node (ref "R12") (pin "1") (pinfunction "1_1") (pintype "passive"))
      (node (ref "U4") (pin "7") (pinfunction "SCL_7") (pintype "bidirectional"))
      (node (ref "U6") (pin "12") (pinfunction "PB4(T)/I2C_SCL(ADC_ETR)_12") (pintype "bidirectional"))
    )
    (net (code "46") (name "SDA") (class "Default")
      (node (ref "CN2") (pin "4") (pinfunction "4_4") (pintype "passive"))
      (node (ref "R13") (pin "1") (pinfunction "1_1") (pintype "passive"))
      (node (ref "U4") (pin "6") (pinfunction "SDA_6") (pintype "bidirectional"))
      (node (ref "U6") (pin "11") (pinfunction "PB5(T)/I2C_SDA(TIM1_BKIN)_11") (pintype "bidirectional"))
    )
    (net (code "47") (name "SWIM") (class "Default")
      (node (ref "CN3") (pin "3") (pinfunction "3_3") (pintype "passive"))
      (node (ref "U6") (pin "18") (pinfunction "PD1(HS)/SWIM_18") (pintype "bidirectional"))
    )
    (net (code "48") (name "TXD") (class "Default")
      (node (ref "CN3") (pin "6") (pinfunction "6_6") (pintype "passive"))
      (node (ref "U6") (pin "2") (pinfunction "PD5(HS)/AIN5/UART1_TX_2") (pintype "bidirectional"))
    )
    (net (code "49") (name "VBUS") (class "Default")
      (node (ref "C31") (pin "1") (pinfunction "1_1") (pintype "passive"))
      (node (ref "CN1") (pin "A9") (pinfunction "VBUS_A9") (pintype "power_in"))
      (node (ref "CN1") (pin "B9") (pinfunction "VBUS_B9") (pintype "power_in"))
      (node (ref "D3") (pin "C") (pinfunction "C_C") (pintype "passive"))
      (node (ref "Q1") (pin "3") (pinfunction "S_3") (pintype "passive"))
      (node (ref "R11") (pin "2") (pinfunction "2_2") (pintype "passive"))
      (node (ref "R15") (pin "2") (pinfunction "2_2") (pintype "passive"))
      (node (ref "R9") (pin "2") (pinfunction "2_2") (pintype "passive"))
      (node (ref "U5") (pin "2") (pinfunction "IN_2") (pintype "passive"))
      (node (ref "U5") (pin "2@1") (pinfunction "IN_2@1") (pintype "passive"))
    )
    (net (code "50") (name "VIN") (class "Default")
      (node (ref "C13") (pin "1") (pinfunction "1_1") (pintype "passive"))
      (node (ref "C14") (pin "1") (pinfunction "1_1") (pintype "passive"))
      (node (ref "C15") (pin "1") (pinfunction "1_1") (pintype "passive"))
      (node (ref "C3") (pin "1") (pinfunction "1_1") (pintype "passive"))
      (node (ref "C35") (pin "1") (pinfunction "1_1") (pintype "passive"))
      (node (ref "C36") (pin "1") (pinfunction "1_1") (pintype "passive"))
      (node (ref "C37") (pin "1") (pinfunction "1_1") (pintype "passive"))
      (node (ref "C38") (pin "1") (pinfunction "1_1") (pintype "passive"))
      (node (ref "C4") (pin "1") (pinfunction "1_1") (pintype "passive"))
      (node (ref "C5") (pin "1") (pinfunction "1_1") (pintype "passive"))
      (node (ref "RS") (pin "2") (pinfunction "2_2") (pintype "passive"))
      (node (ref "U1") (pin "2") (pinfunction "VIN_2") (pintype "passive"))
      (node (ref "U2") (pin "2") (pinfunction "VIN_2") (pintype "passive"))
      (node (ref "U7") (pin "4") (pinfunction "IN-_4") (pintype "passive"))
    )
    (net (code "51") (name "unconnected-(SW1A-S-Pad3)") (class "Default")
      (node (ref "SW1") (pin "3") (pinfunction "S_3") (pintype "passive"))
    )
    (net (code "52") (name "unconnected-(U1-EN-Pad3)") (class "Default")
      (node (ref "U1") (pin "3") (pinfunction "EN_3") (pintype "passive"))
    )
    (net (code "53") (name "unconnected-(U2-EN-Pad3)") (class "Default")
      (node (ref "U2") (pin "3") (pinfunction "EN_3") (pintype "passive"))
    )
    (net (code "54") (name "unconnected-(U3-EN-Pad5)") (class "Default")
      (node (ref "U3") (pin "5") (pinfunction "EN_5") (pintype "passive"))
    )
    (net (code "55") (name "unconnected-(U4-DN-Pad3)") (class "Default")
      (node (ref "U4") (pin "3") (pinfunction "DN_3") (pintype "bidirectional"))
    )
    (net (code "56") (name "unconnected-(U4-DP-Pad2)") (class "Default")
      (node (ref "U4") (pin "2") (pinfunction "DP_2") (pintype "bidirectional"))
    )
    (net (code "57") (name "unconnected-(U6-PA3(HS){slash}TIM2_CH3(SPI_NSS)-Pad10)") (class "Default")
      (node (ref "U6") (pin "10") (pinfunction "PA3(HS)/TIM2_CH3(SPI_NSS)_10") (pintype "bidirectional"))
    )
    (net (code "58") (name "unconnected-(U6-PC6(HS){slash}SPI_MOSI(TIM1_CH1)-Pad16)") (class "Default")
      (node (ref "U6") (pin "16") (pinfunction "PC6(HS)/SPI_MOSI(TIM1_CH1)_16") (pintype "bidirectional"))
    )
    (net (code "59") (name "unconnected-(U6-PC7(HS){slash}SPI_MISO(TIM1_CH2)-Pad17)") (class "Default")
      (node (ref "U6") (pin "17") (pinfunction "PC7(HS)/SPI_MISO(TIM1_CH2)_17") (pintype "bidirectional"))
    )
    (net (code "60") (name "unconnected-(U6-PD3(HS){slash}AIN4{slash}TIM2_CH2{slash}ADC_ETR-Pad20)") (class "Default")
      (node (ref "U6") (pin "20") (pinfunction "PD3(HS)/AIN4/TIM2_CH2/ADC_ETR_20") (pintype "bidirectional"))
    )
  )
)
